# Switches.net
KiCad netlist of a schematic drawn in Altium Designer
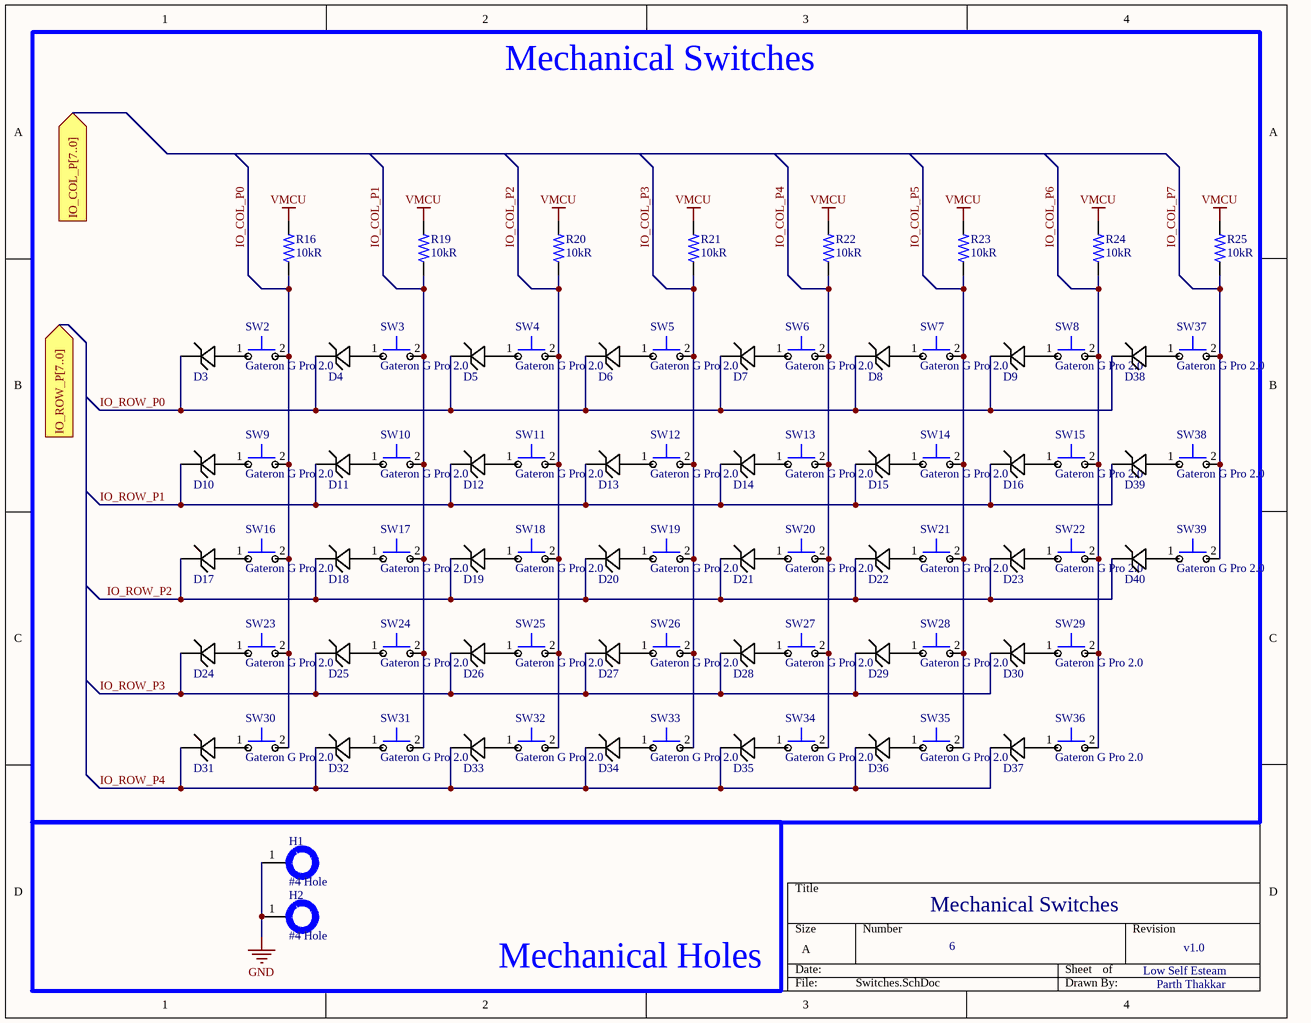
[diagram p0: Switches.SchDoc]

(export (version "E")
  (design (tool "Eeschema 10.0.6"))
  (components
    (comp (ref "D3")
      (value "Diode Schottky")
      (footprint "Diode Schottky")
      (description "Rectifier Diode, Schottky, 1 Phase, 1 Element, 1A, 15V V(RRM), Silicon, DO-214BA")
      (fields
        (field (name "MANUFACTURER") "Microchip")
        (field (name "MANUFACTURER PART NUMBER") "LSM115JE3/TR13")
      )
      (libsource (lib "Keyboard_parts") (part "Diode Schottky"))
    )
    (comp (ref "D4")
      (value "Diode Schottky")
      (footprint "Diode Schottky")
      (description "Rectifier Diode, Schottky, 1 Phase, 1 Element, 1A, 15V V(RRM), Silicon, DO-214BA")
      (fields
        (field (name "MANUFACTURER") "Microchip")
        (field (name "MANUFACTURER PART NUMBER") "LSM115JE3/TR13")
      )
      (libsource (lib "Keyboard_parts") (part "Diode Schottky"))
    )
    (comp (ref "D5")
      (value "Diode Schottky")
      (footprint "Diode Schottky")
      (description "Rectifier Diode, Schottky, 1 Phase, 1 Element, 1A, 15V V(RRM), Silicon, DO-214BA")
      (fields
        (field (name "MANUFACTURER") "Microchip")
        (field (name "MANUFACTURER PART NUMBER") "LSM115JE3/TR13")
      )
      (libsource (lib "Keyboard_parts") (part "Diode Schottky"))
    )
    (comp (ref "D6")
      (value "Diode Schottky")
      (footprint "Diode Schottky")
      (description "Rectifier Diode, Schottky, 1 Phase, 1 Element, 1A, 15V V(RRM), Silicon, DO-214BA")
      (fields
        (field (name "MANUFACTURER") "Microchip")
        (field (name "MANUFACTURER PART NUMBER") "LSM115JE3/TR13")
      )
      (libsource (lib "Keyboard_parts") (part "Diode Schottky"))
    )
    (comp (ref "D7")
      (value "Diode Schottky")
      (footprint "Diode Schottky")
      (description "Rectifier Diode, Schottky, 1 Phase, 1 Element, 1A, 15V V(RRM), Silicon, DO-214BA")
      (fields
        (field (name "MANUFACTURER") "Microchip")
        (field (name "MANUFACTURER PART NUMBER") "LSM115JE3/TR13")
      )
      (libsource (lib "Keyboard_parts") (part "Diode Schottky"))
    )
    (comp (ref "D8")
      (value "Diode Schottky")
      (footprint "Diode Schottky")
      (description "Rectifier Diode, Schottky, 1 Phase, 1 Element, 1A, 15V V(RRM), Silicon, DO-214BA")
      (fields
        (field (name "MANUFACTURER") "Microchip")
        (field (name "MANUFACTURER PART NUMBER") "LSM115JE3/TR13")
      )
      (libsource (lib "Keyboard_parts") (part "Diode Schottky"))
    )
    (comp (ref "D9")
      (value "Diode Schottky")
      (footprint "Diode Schottky")
      (description "Rectifier Diode, Schottky, 1 Phase, 1 Element, 1A, 15V V(RRM), Silicon, DO-214BA")
      (fields
        (field (name "MANUFACTURER") "Microchip")
        (field (name "MANUFACTURER PART NUMBER") "LSM115JE3/TR13")
      )
      (libsource (lib "Keyboard_parts") (part "Diode Schottky"))
    )
    (comp (ref "D10")
      (value "Diode Schottky")
      (footprint "Diode Schottky")
      (description "Rectifier Diode, Schottky, 1 Phase, 1 Element, 1A, 15V V(RRM), Silicon, DO-214BA")
      (fields
        (field (name "MANUFACTURER") "Microchip")
        (field (name "MANUFACTURER PART NUMBER") "LSM115JE3/TR13")
      )
      (libsource (lib "Keyboard_parts") (part "Diode Schottky"))
    )
    (comp (ref "D11")
      (value "Diode Schottky")
      (footprint "Diode Schottky")
      (description "Rectifier Diode, Schottky, 1 Phase, 1 Element, 1A, 15V V(RRM), Silicon, DO-214BA")
      (fields
        (field (name "MANUFACTURER") "Microchip")
        (field (name "MANUFACTURER PART NUMBER") "LSM115JE3/TR13")
      )
      (libsource (lib "Keyboard_parts") (part "Diode Schottky"))
    )
    (comp (ref "D12")
      (value "Diode Schottky")
      (footprint "Diode Schottky")
      (description "Rectifier Diode, Schottky, 1 Phase, 1 Element, 1A, 15V V(RRM), Silicon, DO-214BA")
      (fields
        (field (name "MANUFACTURER") "Microchip")
        (field (name "MANUFACTURER PART NUMBER") "LSM115JE3/TR13")
      )
      (libsource (lib "Keyboard_parts") (part "Diode Schottky"))
    )
    (comp (ref "D13")
      (value "Diode Schottky")
      (footprint "Diode Schottky")
      (description "Rectifier Diode, Schottky, 1 Phase, 1 Element, 1A, 15V V(RRM), Silicon, DO-214BA")
      (fields
        (field (name "MANUFACTURER") "Microchip")
        (field (name "MANUFACTURER PART NUMBER") "LSM115JE3/TR13")
      )
      (libsource (lib "Keyboard_parts") (part "Diode Schottky"))
    )
    (comp (ref "D14")
      (value "Diode Schottky")
      (footprint "Diode Schottky")
      (description "Rectifier Diode, Schottky, 1 Phase, 1 Element, 1A, 15V V(RRM), Silicon, DO-214BA")
      (fields
        (field (name "MANUFACTURER") "Microchip")
        (field (name "MANUFACTURER PART NUMBER") "LSM115JE3/TR13")
      )
      (libsource (lib "Keyboard_parts") (part "Diode Schottky"))
    )
    (comp (ref "D15")
      (value "Diode Schottky")
      (footprint "Diode Schottky")
      (description "Rectifier Diode, Schottky, 1 Phase, 1 Element, 1A, 15V V(RRM), Silicon, DO-214BA")
      (fields
        (field (name "MANUFACTURER") "Microchip")
        (field (name "MANUFACTURER PART NUMBER") "LSM115JE3/TR13")
      )
      (libsource (lib "Keyboard_parts") (part "Diode Schottky"))
    )
    (comp (ref "D16")
      (value "Diode Schottky")
      (footprint "Diode Schottky")
      (description "Rectifier Diode, Schottky, 1 Phase, 1 Element, 1A, 15V V(RRM), Silicon, DO-214BA")
      (fields
        (field (name "MANUFACTURER") "Microchip")
        (field (name "MANUFACTURER PART NUMBER") "LSM115JE3/TR13")
      )
      (libsource (lib "Keyboard_parts") (part "Diode Schottky"))
    )
    (comp (ref "D17")
      (value "Diode Schottky")
      (footprint "Diode Schottky")
      (description "Rectifier Diode, Schottky, 1 Phase, 1 Element, 1A, 15V V(RRM), Silicon, DO-214BA")
      (fields
        (field (name "MANUFACTURER") "Microchip")
        (field (name "MANUFACTURER PART NUMBER") "LSM115JE3/TR13")
      )
      (libsource (lib "Keyboard_parts") (part "Diode Schottky"))
    )
    (comp (ref "D18")
      (value "Diode Schottky")
      (footprint "Diode Schottky")
      (description "Rectifier Diode, Schottky, 1 Phase, 1 Element, 1A, 15V V(RRM), Silicon, DO-214BA")
      (fields
        (field (name "MANUFACTURER") "Microchip")
        (field (name "MANUFACTURER PART NUMBER") "LSM115JE3/TR13")
      )
      (libsource (lib "Keyboard_parts") (part "Diode Schottky"))
    )
    (comp (ref "D19")
      (value "Diode Schottky")
      (footprint "Diode Schottky")
      (description "Rectifier Diode, Schottky, 1 Phase, 1 Element, 1A, 15V V(RRM), Silicon, DO-214BA")
      (fields
        (field (name "MANUFACTURER") "Microchip")
        (field (name "MANUFACTURER PART NUMBER") "LSM115JE3/TR13")
      )
      (libsource (lib "Keyboard_parts") (part "Diode Schottky"))
    )
    (comp (ref "D20")
      (value "Diode Schottky")
      (footprint "Diode Schottky")
      (description "Rectifier Diode, Schottky, 1 Phase, 1 Element, 1A, 15V V(RRM), Silicon, DO-214BA")
      (fields
        (field (name "MANUFACTURER") "Microchip")
        (field (name "MANUFACTURER PART NUMBER") "LSM115JE3/TR13")
      )
      (libsource (lib "Keyboard_parts") (part "Diode Schottky"))
    )
    (comp (ref "D21")
      (value "Diode Schottky")
      (footprint "Diode Schottky")
      (description "Rectifier Diode, Schottky, 1 Phase, 1 Element, 1A, 15V V(RRM), Silicon, DO-214BA")
      (fields
        (field (name "MANUFACTURER") "Microchip")
        (field (name "MANUFACTURER PART NUMBER") "LSM115JE3/TR13")
      )
      (libsource (lib "Keyboard_parts") (part "Diode Schottky"))
    )
    (comp (ref "D22")
      (value "Diode Schottky")
      (footprint "Diode Schottky")
      (description "Rectifier Diode, Schottky, 1 Phase, 1 Element, 1A, 15V V(RRM), Silicon, DO-214BA")
      (fields
        (field (name "MANUFACTURER") "Microchip")
        (field (name "MANUFACTURER PART NUMBER") "LSM115JE3/TR13")
      )
      (libsource (lib "Keyboard_parts") (part "Diode Schottky"))
    )
    (comp (ref "D23")
      (value "Diode Schottky")
      (footprint "Diode Schottky")
      (description "Rectifier Diode, Schottky, 1 Phase, 1 Element, 1A, 15V V(RRM), Silicon, DO-214BA")
      (fields
        (field (name "MANUFACTURER") "Microchip")
        (field (name "MANUFACTURER PART NUMBER") "LSM115JE3/TR13")
      )
      (libsource (lib "Keyboard_parts") (part "Diode Schottky"))
    )
    (comp (ref "D24")
      (value "Diode Schottky")
      (footprint "Diode Schottky")
      (description "Rectifier Diode, Schottky, 1 Phase, 1 Element, 1A, 15V V(RRM), Silicon, DO-214BA")
      (fields
        (field (name "MANUFACTURER") "Microchip")
        (field (name "MANUFACTURER PART NUMBER") "LSM115JE3/TR13")
      )
      (libsource (lib "Keyboard_parts") (part "Diode Schottky"))
    )
    (comp (ref "D25")
      (value "Diode Schottky")
      (footprint "Diode Schottky")
      (description "Rectifier Diode, Schottky, 1 Phase, 1 Element, 1A, 15V V(RRM), Silicon, DO-214BA")
      (fields
        (field (name "MANUFACTURER") "Microchip")
        (field (name "MANUFACTURER PART NUMBER") "LSM115JE3/TR13")
      )
      (libsource (lib "Keyboard_parts") (part "Diode Schottky"))
    )
    (comp (ref "D26")
      (value "Diode Schottky")
      (footprint "Diode Schottky")
      (description "Rectifier Diode, Schottky, 1 Phase, 1 Element, 1A, 15V V(RRM), Silicon, DO-214BA")
      (fields
        (field (name "MANUFACTURER") "Microchip")
        (field (name "MANUFACTURER PART NUMBER") "LSM115JE3/TR13")
      )
      (libsource (lib "Keyboard_parts") (part "Diode Schottky"))
    )
    (comp (ref "D27")
      (value "Diode Schottky")
      (footprint "Diode Schottky")
      (description "Rectifier Diode, Schottky, 1 Phase, 1 Element, 1A, 15V V(RRM), Silicon, DO-214BA")
      (fields
        (field (name "MANUFACTURER") "Microchip")
        (field (name "MANUFACTURER PART NUMBER") "LSM115JE3/TR13")
      )
      (libsource (lib "Keyboard_parts") (part "Diode Schottky"))
    )
    (comp (ref "D28")
      (value "Diode Schottky")
      (footprint "Diode Schottky")
      (description "Rectifier Diode, Schottky, 1 Phase, 1 Element, 1A, 15V V(RRM), Silicon, DO-214BA")
      (fields
        (field (name "MANUFACTURER") "Microchip")
        (field (name "MANUFACTURER PART NUMBER") "LSM115JE3/TR13")
      )
      (libsource (lib "Keyboard_parts") (part "Diode Schottky"))
    )
    (comp (ref "D29")
      (value "Diode Schottky")
      (footprint "Diode Schottky")
      (description "Rectifier Diode, Schottky, 1 Phase, 1 Element, 1A, 15V V(RRM), Silicon, DO-214BA")
      (fields
        (field (name "MANUFACTURER") "Microchip")
        (field (name "MANUFACTURER PART NUMBER") "LSM115JE3/TR13")
      )
      (libsource (lib "Keyboard_parts") (part "Diode Schottky"))
    )
    (comp (ref "D30")
      (value "Diode Schottky")
      (footprint "Diode Schottky")
      (description "Rectifier Diode, Schottky, 1 Phase, 1 Element, 1A, 15V V(RRM), Silicon, DO-214BA")
      (fields
        (field (name "MANUFACTURER") "Microchip")
        (field (name "MANUFACTURER PART NUMBER") "LSM115JE3/TR13")
      )
      (libsource (lib "Keyboard_parts") (part "Diode Schottky"))
    )
    (comp (ref "D31")
      (value "Diode Schottky")
      (footprint "Diode Schottky")
      (description "Rectifier Diode, Schottky, 1 Phase, 1 Element, 1A, 15V V(RRM), Silicon, DO-214BA")
      (fields
        (field (name "MANUFACTURER") "Microchip")
        (field (name "MANUFACTURER PART NUMBER") "LSM115JE3/TR13")
      )
      (libsource (lib "Keyboard_parts") (part "Diode Schottky"))
    )
    (comp (ref "D32")
      (value "Diode Schottky")
      (footprint "Diode Schottky")
      (description "Rectifier Diode, Schottky, 1 Phase, 1 Element, 1A, 15V V(RRM), Silicon, DO-214BA")
      (fields
        (field (name "MANUFACTURER") "Microchip")
        (field (name "MANUFACTURER PART NUMBER") "LSM115JE3/TR13")
      )
      (libsource (lib "Keyboard_parts") (part "Diode Schottky"))
    )
    (comp (ref "D33")
      (value "Diode Schottky")
      (footprint "Diode Schottky")
      (description "Rectifier Diode, Schottky, 1 Phase, 1 Element, 1A, 15V V(RRM), Silicon, DO-214BA")
      (fields
        (field (name "MANUFACTURER") "Microchip")
        (field (name "MANUFACTURER PART NUMBER") "LSM115JE3/TR13")
      )
      (libsource (lib "Keyboard_parts") (part "Diode Schottky"))
    )
    (comp (ref "D34")
      (value "Diode Schottky")
      (footprint "Diode Schottky")
      (description "Rectifier Diode, Schottky, 1 Phase, 1 Element, 1A, 15V V(RRM), Silicon, DO-214BA")
      (fields
        (field (name "MANUFACTURER") "Microchip")
        (field (name "MANUFACTURER PART NUMBER") "LSM115JE3/TR13")
      )
      (libsource (lib "Keyboard_parts") (part "Diode Schottky"))
    )
    (comp (ref "D35")
      (value "Diode Schottky")
      (footprint "Diode Schottky")
      (description "Rectifier Diode, Schottky, 1 Phase, 1 Element, 1A, 15V V(RRM), Silicon, DO-214BA")
      (fields
        (field (name "MANUFACTURER") "Microchip")
        (field (name "MANUFACTURER PART NUMBER") "LSM115JE3/TR13")
      )
      (libsource (lib "Keyboard_parts") (part "Diode Schottky"))
    )
    (comp (ref "D36")
      (value "Diode Schottky")
      (footprint "Diode Schottky")
      (description "Rectifier Diode, Schottky, 1 Phase, 1 Element, 1A, 15V V(RRM), Silicon, DO-214BA")
      (fields
        (field (name "MANUFACTURER") "Microchip")
        (field (name "MANUFACTURER PART NUMBER") "LSM115JE3/TR13")
      )
      (libsource (lib "Keyboard_parts") (part "Diode Schottky"))
    )
    (comp (ref "D37")
      (value "Diode Schottky")
      (footprint "Diode Schottky")
      (description "Rectifier Diode, Schottky, 1 Phase, 1 Element, 1A, 15V V(RRM), Silicon, DO-214BA")
      (fields
        (field (name "MANUFACTURER") "Microchip")
        (field (name "MANUFACTURER PART NUMBER") "LSM115JE3/TR13")
      )
      (libsource (lib "Keyboard_parts") (part "Diode Schottky"))
    )
    (comp (ref "D38")
      (value "Diode Schottky")
      (footprint "Diode Schottky")
      (description "Rectifier Diode, Schottky, 1 Phase, 1 Element, 1A, 15V V(RRM), Silicon, DO-214BA")
      (fields
        (field (name "MANUFACTURER") "Microchip")
        (field (name "MANUFACTURER PART NUMBER") "LSM115JE3/TR13")
      )
      (libsource (lib "Keyboard_parts") (part "Diode Schottky"))
    )
    (comp (ref "D39")
      (value "Diode Schottky")
      (footprint "Diode Schottky")
      (description "Rectifier Diode, Schottky, 1 Phase, 1 Element, 1A, 15V V(RRM), Silicon, DO-214BA")
      (fields
        (field (name "MANUFACTURER") "Microchip")
        (field (name "MANUFACTURER PART NUMBER") "LSM115JE3/TR13")
      )
      (libsource (lib "Keyboard_parts") (part "Diode Schottky"))
    )
    (comp (ref "D40")
      (value "Diode Schottky")
      (footprint "Diode Schottky")
      (description "Rectifier Diode, Schottky, 1 Phase, 1 Element, 1A, 15V V(RRM), Silicon, DO-214BA")
      (fields
        (field (name "MANUFACTURER") "Microchip")
        (field (name "MANUFACTURER PART NUMBER") "LSM115JE3/TR13")
      )
      (libsource (lib "Keyboard_parts") (part "Diode Schottky"))
    )
    (comp (ref "H1") (value "#4 Hole") (footprint "Hole") (libsource (lib "Keyboard_parts") (part "HOLE_#4")))
    (comp (ref "H2") (value "#4 Hole") (footprint "Hole") (libsource (lib "Keyboard_parts") (part "HOLE_#4")))
    (comp (ref "R16")
      (value "10kR")
      (footprint "Resistor 0603")
      (fields
        (field (name "MANUFACTURER") "Yageo")
        (field (name "MANUFACTURER PART NUMBER") "RC0603FR-0710KL")
        (field (name "TOLERANCE") "1%")
      )
      (libsource (lib "Keyboard_parts") (part "RES 10K 0603"))
    )
    (comp (ref "R19")
      (value "10kR")
      (footprint "Resistor 0603")
      (fields
        (field (name "MANUFACTURER") "Yageo")
        (field (name "MANUFACTURER PART NUMBER") "RC0603FR-0710KL")
        (field (name "TOLERANCE") "1%")
      )
      (libsource (lib "Keyboard_parts") (part "RES 10K 0603"))
    )
    (comp (ref "R20")
      (value "10kR")
      (footprint "Resistor 0603")
      (fields
        (field (name "MANUFACTURER") "Yageo")
        (field (name "MANUFACTURER PART NUMBER") "RC0603FR-0710KL")
        (field (name "TOLERANCE") "1%")
      )
      (libsource (lib "Keyboard_parts") (part "RES 10K 0603"))
    )
    (comp (ref "R21")
      (value "10kR")
      (footprint "Resistor 0603")
      (fields
        (field (name "MANUFACTURER") "Yageo")
        (field (name "MANUFACTURER PART NUMBER") "RC0603FR-0710KL")
        (field (name "TOLERANCE") "1%")
      )
      (libsource (lib "Keyboard_parts") (part "RES 10K 0603"))
    )
    (comp (ref "R22")
      (value "10kR")
      (footprint "Resistor 0603")
      (fields
        (field (name "MANUFACTURER") "Yageo")
        (field (name "MANUFACTURER PART NUMBER") "RC0603FR-0710KL")
        (field (name "TOLERANCE") "1%")
      )
      (libsource (lib "Keyboard_parts") (part "RES 10K 0603"))
    )
    (comp (ref "R23")
      (value "10kR")
      (footprint "Resistor 0603")
      (fields
        (field (name "MANUFACTURER") "Yageo")
        (field (name "MANUFACTURER PART NUMBER") "RC0603FR-0710KL")
        (field (name "TOLERANCE") "1%")
      )
      (libsource (lib "Keyboard_parts") (part "RES 10K 0603"))
    )
    (comp (ref "R24")
      (value "10kR")
      (footprint "Resistor 0603")
      (fields
        (field (name "MANUFACTURER") "Yageo")
        (field (name "MANUFACTURER PART NUMBER") "RC0603FR-0710KL")
        (field (name "TOLERANCE") "1%")
      )
      (libsource (lib "Keyboard_parts") (part "RES 10K 0603"))
    )
    (comp (ref "R25")
      (value "10kR")
      (footprint "Resistor 0603")
      (fields
        (field (name "MANUFACTURER") "Yageo")
        (field (name "MANUFACTURER PART NUMBER") "RC0603FR-0710KL")
        (field (name "TOLERANCE") "1%")
      )
      (libsource (lib "Keyboard_parts") (part "RES 10K 0603"))
    )
    (comp (ref "SW2")
      (value "Gateron G Pro 2.0")
      (footprint "Mechanical Switch")
      (description "Gateron G Pro 2.0, The 3-Pin switches are compatible with any 3-Pin/5-Pin MX mechanical keyboard")
      (libsource (lib "Keyboard_parts") (part "Gateron G Pro 2.0"))
    )
    (comp (ref "SW3")
      (value "Gateron G Pro 2.0")
      (footprint "Mechanical Switch")
      (description "Gateron G Pro 2.0, The 3-Pin switches are compatible with any 3-Pin/5-Pin MX mechanical keyboard")
      (libsource (lib "Keyboard_parts") (part "Gateron G Pro 2.0"))
    )
    (comp (ref "SW4")
      (value "Gateron G Pro 2.0")
      (footprint "Mechanical Switch")
      (description "Gateron G Pro 2.0, The 3-Pin switches are compatible with any 3-Pin/5-Pin MX mechanical keyboard")
      (libsource (lib "Keyboard_parts") (part "Gateron G Pro 2.0"))
    )
    (comp (ref "SW5")
      (value "Gateron G Pro 2.0")
      (footprint "Mechanical Switch")
      (description "Gateron G Pro 2.0, The 3-Pin switches are compatible with any 3-Pin/5-Pin MX mechanical keyboard")
      (libsource (lib "Keyboard_parts") (part "Gateron G Pro 2.0"))
    )
    (comp (ref "SW6")
      (value "Gateron G Pro 2.0")
      (footprint "Mechanical Switch")
      (description "Gateron G Pro 2.0, The 3-Pin switches are compatible with any 3-Pin/5-Pin MX mechanical keyboard")
      (libsource (lib "Keyboard_parts") (part "Gateron G Pro 2.0"))
    )
    (comp (ref "SW7")
      (value "Gateron G Pro 2.0")
      (footprint "Mechanical Switch")
      (description "Gateron G Pro 2.0, The 3-Pin switches are compatible with any 3-Pin/5-Pin MX mechanical keyboard")
      (libsource (lib "Keyboard_parts") (part "Gateron G Pro 2.0"))
    )
    (comp (ref "SW8")
      (value "Gateron G Pro 2.0")
      (footprint "Mechanical Switch")
      (description "Gateron G Pro 2.0, The 3-Pin switches are compatible with any 3-Pin/5-Pin MX mechanical keyboard")
      (libsource (lib "Keyboard_parts") (part "Gateron G Pro 2.0"))
    )
    (comp (ref "SW9")
      (value "Gateron G Pro 2.0")
      (footprint "Mechanical Switch")
      (description "Gateron G Pro 2.0, The 3-Pin switches are compatible with any 3-Pin/5-Pin MX mechanical keyboard")
      (libsource (lib "Keyboard_parts") (part "Gateron G Pro 2.0"))
    )
    (comp (ref "SW10")
      (value "Gateron G Pro 2.0")
      (footprint "Mechanical Switch")
      (description "Gateron G Pro 2.0, The 3-Pin switches are compatible with any 3-Pin/5-Pin MX mechanical keyboard")
      (libsource (lib "Keyboard_parts") (part "Gateron G Pro 2.0"))
    )
    (comp (ref "SW11")
      (value "Gateron G Pro 2.0")
      (footprint "Mechanical Switch")
      (description "Gateron G Pro 2.0, The 3-Pin switches are compatible with any 3-Pin/5-Pin MX mechanical keyboard")
      (libsource (lib "Keyboard_parts") (part "Gateron G Pro 2.0"))
    )
    (comp (ref "SW12")
      (value "Gateron G Pro 2.0")
      (footprint "Mechanical Switch")
      (description "Gateron G Pro 2.0, The 3-Pin switches are compatible with any 3-Pin/5-Pin MX mechanical keyboard")
      (libsource (lib "Keyboard_parts") (part "Gateron G Pro 2.0"))
    )
    (comp (ref "SW13")
      (value "Gateron G Pro 2.0")
      (footprint "Mechanical Switch")
      (description "Gateron G Pro 2.0, The 3-Pin switches are compatible with any 3-Pin/5-Pin MX mechanical keyboard")
      (libsource (lib "Keyboard_parts") (part "Gateron G Pro 2.0"))
    )
    (comp (ref "SW14")
      (value "Gateron G Pro 2.0")
      (footprint "Mechanical Switch")
      (description "Gateron G Pro 2.0, The 3-Pin switches are compatible with any 3-Pin/5-Pin MX mechanical keyboard")
      (libsource (lib "Keyboard_parts") (part "Gateron G Pro 2.0"))
    )
    (comp (ref "SW15")
      (value "Gateron G Pro 2.0")
      (footprint "Mechanical Switch")
      (description "Gateron G Pro 2.0, The 3-Pin switches are compatible with any 3-Pin/5-Pin MX mechanical keyboard")
      (libsource (lib "Keyboard_parts") (part "Gateron G Pro 2.0"))
    )
    (comp (ref "SW16")
      (value "Gateron G Pro 2.0")
      (footprint "Mechanical Switch")
      (description "Gateron G Pro 2.0, The 3-Pin switches are compatible with any 3-Pin/5-Pin MX mechanical keyboard")
      (libsource (lib "Keyboard_parts") (part "Gateron G Pro 2.0"))
    )
    (comp (ref "SW17")
      (value "Gateron G Pro 2.0")
      (footprint "Mechanical Switch")
      (description "Gateron G Pro 2.0, The 3-Pin switches are compatible with any 3-Pin/5-Pin MX mechanical keyboard")
      (libsource (lib "Keyboard_parts") (part "Gateron G Pro 2.0"))
    )
    (comp (ref "SW18")
      (value "Gateron G Pro 2.0")
      (footprint "Mechanical Switch")
      (description "Gateron G Pro 2.0, The 3-Pin switches are compatible with any 3-Pin/5-Pin MX mechanical keyboard")
      (libsource (lib "Keyboard_parts") (part "Gateron G Pro 2.0"))
    )
    (comp (ref "SW19")
      (value "Gateron G Pro 2.0")
      (footprint "Mechanical Switch")
      (description "Gateron G Pro 2.0, The 3-Pin switches are compatible with any 3-Pin/5-Pin MX mechanical keyboard")
      (libsource (lib "Keyboard_parts") (part "Gateron G Pro 2.0"))
    )
    (comp (ref "SW20")
      (value "Gateron G Pro 2.0")
      (footprint "Mechanical Switch")
      (description "Gateron G Pro 2.0, The 3-Pin switches are compatible with any 3-Pin/5-Pin MX mechanical keyboard")
      (libsource (lib "Keyboard_parts") (part "Gateron G Pro 2.0"))
    )
    (comp (ref "SW21")
      (value "Gateron G Pro 2.0")
      (footprint "Mechanical Switch")
      (description "Gateron G Pro 2.0, The 3-Pin switches are compatible with any 3-Pin/5-Pin MX mechanical keyboard")
      (libsource (lib "Keyboard_parts") (part "Gateron G Pro 2.0"))
    )
    (comp (ref "SW22")
      (value "Gateron G Pro 2.0")
      (footprint "Mechanical Switch")
      (description "Gateron G Pro 2.0, The 3-Pin switches are compatible with any 3-Pin/5-Pin MX mechanical keyboard")
      (libsource (lib "Keyboard_parts") (part "Gateron G Pro 2.0"))
    )
    (comp (ref "SW23")
      (value "Gateron G Pro 2.0")
      (footprint "Mechanical Switch")
      (description "Gateron G Pro 2.0, The 3-Pin switches are compatible with any 3-Pin/5-Pin MX mechanical keyboard")
      (libsource (lib "Keyboard_parts") (part "Gateron G Pro 2.0"))
    )
    (comp (ref "SW24")
      (value "Gateron G Pro 2.0")
      (footprint "Mechanical Switch")
      (description "Gateron G Pro 2.0, The 3-Pin switches are compatible with any 3-Pin/5-Pin MX mechanical keyboard")
      (libsource (lib "Keyboard_parts") (part "Gateron G Pro 2.0"))
    )
    (comp (ref "SW25")
      (value "Gateron G Pro 2.0")
      (footprint "Mechanical Switch")
      (description "Gateron G Pro 2.0, The 3-Pin switches are compatible with any 3-Pin/5-Pin MX mechanical keyboard")
      (libsource (lib "Keyboard_parts") (part "Gateron G Pro 2.0"))
    )
    (comp (ref "SW26")
      (value "Gateron G Pro 2.0")
      (footprint "Mechanical Switch")
      (description "Gateron G Pro 2.0, The 3-Pin switches are compatible with any 3-Pin/5-Pin MX mechanical keyboard")
      (libsource (lib "Keyboard_parts") (part "Gateron G Pro 2.0"))
    )
    (comp (ref "SW27")
      (value "Gateron G Pro 2.0")
      (footprint "Mechanical Switch")
      (description "Gateron G Pro 2.0, The 3-Pin switches are compatible with any 3-Pin/5-Pin MX mechanical keyboard")
      (libsource (lib "Keyboard_parts") (part "Gateron G Pro 2.0"))
    )
    (comp (ref "SW28")
      (value "Gateron G Pro 2.0")
      (footprint "Mechanical Switch")
      (description "Gateron G Pro 2.0, The 3-Pin switches are compatible with any 3-Pin/5-Pin MX mechanical keyboard")
      (libsource (lib "Keyboard_parts") (part "Gateron G Pro 2.0"))
    )
    (comp (ref "SW29")
      (value "Gateron G Pro 2.0")
      (footprint "Mechanical Switch")
      (description "Gateron G Pro 2.0, The 3-Pin switches are compatible with any 3-Pin/5-Pin MX mechanical keyboard")
      (libsource (lib "Keyboard_parts") (part "Gateron G Pro 2.0"))
    )
    (comp (ref "SW30")
      (value "Gateron G Pro 2.0")
      (footprint "Mechanical Switch")
      (description "Gateron G Pro 2.0, The 3-Pin switches are compatible with any 3-Pin/5-Pin MX mechanical keyboard")
      (libsource (lib "Keyboard_parts") (part "Gateron G Pro 2.0"))
    )
    (comp (ref "SW31")
      (value "Gateron G Pro 2.0")
      (footprint "Mechanical Switch")
      (description "Gateron G Pro 2.0, The 3-Pin switches are compatible with any 3-Pin/5-Pin MX mechanical keyboard")
      (libsource (lib "Keyboard_parts") (part "Gateron G Pro 2.0"))
    )
    (comp (ref "SW32")
      (value "Gateron G Pro 2.0")
      (footprint "Mechanical Switch")
      (description "Gateron G Pro 2.0, The 3-Pin switches are compatible with any 3-Pin/5-Pin MX mechanical keyboard")
      (libsource (lib "Keyboard_parts") (part "Gateron G Pro 2.0"))
    )
    (comp (ref "SW33")
      (value "Gateron G Pro 2.0")
      (footprint "Mechanical Switch")
      (description "Gateron G Pro 2.0, The 3-Pin switches are compatible with any 3-Pin/5-Pin MX mechanical keyboard")
      (libsource (lib "Keyboard_parts") (part "Gateron G Pro 2.0"))
    )
    (comp (ref "SW34")
      (value "Gateron G Pro 2.0")
      (footprint "Mechanical Switch")
      (description "Gateron G Pro 2.0, The 3-Pin switches are compatible with any 3-Pin/5-Pin MX mechanical keyboard")
      (libsource (lib "Keyboard_parts") (part "Gateron G Pro 2.0"))
    )
    (comp (ref "SW35")
      (value "Gateron G Pro 2.0")
      (footprint "Mechanical Switch")
      (description "Gateron G Pro 2.0, The 3-Pin switches are compatible with any 3-Pin/5-Pin MX mechanical keyboard")
      (libsource (lib "Keyboard_parts") (part "Gateron G Pro 2.0"))
    )
    (comp (ref "SW36")
      (value "Gateron G Pro 2.0")
      (footprint "Mechanical Switch")
      (description "Gateron G Pro 2.0, The 3-Pin switches are compatible with any 3-Pin/5-Pin MX mechanical keyboard")
      (libsource (lib "Keyboard_parts") (part "Gateron G Pro 2.0"))
    )
    (comp (ref "SW37")
      (value "Gateron G Pro 2.0")
      (footprint "Mechanical Switch")
      (description "Gateron G Pro 2.0, The 3-Pin switches are compatible with any 3-Pin/5-Pin MX mechanical keyboard")
      (libsource (lib "Keyboard_parts") (part "Gateron G Pro 2.0"))
    )
    (comp (ref "SW38")
      (value "Gateron G Pro 2.0")
      (footprint "Mechanical Switch")
      (description "Gateron G Pro 2.0, The 3-Pin switches are compatible with any 3-Pin/5-Pin MX mechanical keyboard")
      (libsource (lib "Keyboard_parts") (part "Gateron G Pro 2.0"))
    )
    (comp (ref "SW39")
      (value "Gateron G Pro 2.0")
      (footprint "Mechanical Switch")
      (description "Gateron G Pro 2.0, The 3-Pin switches are compatible with any 3-Pin/5-Pin MX mechanical keyboard")
      (libsource (lib "Keyboard_parts") (part "Gateron G Pro 2.0"))
    )
  )
  (nets
    (net (code "4") (name "/IO_COL_P0") (class "Default")
      (node (ref "R16") (pin "1") (pinfunction "1_1") (pintype "passive"))
      (node (ref "SW16") (pin "2") (pinfunction "2_2") (pintype "passive"))
      (node (ref "SW2") (pin "2") (pinfunction "2_2") (pintype "passive"))
      (node (ref "SW23") (pin "2") (pinfunction "2_2") (pintype "passive"))
      (node (ref "SW30") (pin "2") (pinfunction "2_2") (pintype "passive"))
      (node (ref "SW9") (pin "2") (pinfunction "2_2") (pintype "passive"))
    )
    (net (code "5") (name "/IO_COL_P1") (class "Default")
      (node (ref "R19") (pin "1") (pinfunction "1_1") (pintype "passive"))
      (node (ref "SW10") (pin "2") (pinfunction "2_2") (pintype "passive"))
      (node (ref "SW17") (pin "2") (pinfunction "2_2") (pintype "passive"))
      (node (ref "SW24") (pin "2") (pinfunction "2_2") (pintype "passive"))
      (node (ref "SW3") (pin "2") (pinfunction "2_2") (pintype "passive"))
      (node (ref "SW31") (pin "2") (pinfunction "2_2") (pintype "passive"))
    )
    (net (code "6") (name "/IO_COL_P2") (class "Default")
      (node (ref "R20") (pin "1") (pinfunction "1_1") (pintype "passive"))
      (node (ref "SW11") (pin "2") (pinfunction "2_2") (pintype "passive"))
      (node (ref "SW18") (pin "2") (pinfunction "2_2") (pintype "passive"))
      (node (ref "SW25") (pin "2") (pinfunction "2_2") (pintype "passive"))
      (node (ref "SW32") (pin "2") (pinfunction "2_2") (pintype "passive"))
      (node (ref "SW4") (pin "2") (pinfunction "2_2") (pintype "passive"))
    )
    (net (code "7") (name "/IO_COL_P3") (class "Default")
      (node (ref "R21") (pin "1") (pinfunction "1_1") (pintype "passive"))
      (node (ref "SW12") (pin "2") (pinfunction "2_2") (pintype "passive"))
      (node (ref "SW19") (pin "2") (pinfunction "2_2") (pintype "passive"))
      (node (ref "SW26") (pin "2") (pinfunction "2_2") (pintype "passive"))
      (node (ref "SW33") (pin "2") (pinfunction "2_2") (pintype "passive"))
      (node (ref "SW5") (pin "2") (pinfunction "2_2") (pintype "passive"))
    )
    (net (code "8") (name "/IO_COL_P4") (class "Default")
      (node (ref "R22") (pin "1") (pinfunction "1_1") (pintype "passive"))
      (node (ref "SW13") (pin "2") (pinfunction "2_2") (pintype "passive"))
      (node (ref "SW20") (pin "2") (pinfunction "2_2") (pintype "passive"))
      (node (ref "SW27") (pin "2") (pinfunction "2_2") (pintype "passive"))
      (node (ref "SW34") (pin "2") (pinfunction "2_2") (pintype "passive"))
      (node (ref "SW6") (pin "2") (pinfunction "2_2") (pintype "passive"))
    )
    (net (code "9") (name "/IO_COL_P5") (class "Default")
      (node (ref "R23") (pin "1") (pinfunction "1_1") (pintype "passive"))
      (node (ref "SW14") (pin "2") (pinfunction "2_2") (pintype "passive"))
      (node (ref "SW21") (pin "2") (pinfunction "2_2") (pintype "passive"))
      (node (ref "SW28") (pin "2") (pinfunction "2_2") (pintype "passive"))
      (node (ref "SW35") (pin "2") (pinfunction "2_2") (pintype "passive"))
      (node (ref "SW7") (pin "2") (pinfunction "2_2") (pintype "passive"))
    )
    (net (code "10") (name "/IO_COL_P6") (class "Default")
      (node (ref "R24") (pin "1") (pinfunction "1_1") (pintype "passive"))
      (node (ref "SW15") (pin "2") (pinfunction "2_2") (pintype "passive"))
      (node (ref "SW22") (pin "2") (pinfunction "2_2") (pintype "passive"))
      (node (ref "SW29") (pin "2") (pinfunction "2_2") (pintype "passive"))
      (node (ref "SW36") (pin "2") (pinfunction "2_2") (pintype "passive"))
      (node (ref "SW8") (pin "2") (pinfunction "2_2") (pintype "passive"))
    )
    (net (code "11") (name "/IO_COL_P7") (class "Default")
      (node (ref "R25") (pin "1") (pinfunction "1_1") (pintype "passive"))
      (node (ref "SW37") (pin "2") (pinfunction "2_2") (pintype "passive"))
      (node (ref "SW38") (pin "2") (pinfunction "2_2") (pintype "passive"))
      (node (ref "SW39") (pin "2") (pinfunction "2_2") (pintype "passive"))
    )
    (net (code "13") (name "/IO_ROW_P0") (class "Default")
      (node (ref "D3") (pin "1") (pinfunction "1_1") (pintype "passive"))
      (node (ref "D38") (pin "1") (pinfunction "1_1") (pintype "passive"))
      (node (ref "D4") (pin "1") (pinfunction "1_1") (pintype "passive"))
      (node (ref "D5") (pin "1") (pinfunction "1_1") (pintype "passive"))
      (node (ref "D6") (pin "1") (pinfunction "1_1") (pintype "passive"))
      (node (ref "D7") (pin "1") (pinfunction "1_1") (pintype "passive"))
      (node (ref "D8") (pin "1") (pinfunction "1_1") (pintype "passive"))
      (node (ref "D9") (pin "1") (pinfunction "1_1") (pintype "passive"))
    )
    (net (code "14") (name "/IO_ROW_P1") (class "Default")
      (node (ref "D10") (pin "1") (pinfunction "1_1") (pintype "passive"))
      (node (ref "D11") (pin "1") (pinfunction "1_1") (pintype "passive"))
      (node (ref "D12") (pin "1") (pinfunction "1_1") (pintype "passive"))
      (node (ref "D13") (pin "1") (pinfunction "1_1") (pintype "passive"))
      (node (ref "D14") (pin "1") (pinfunction "1_1") (pintype "passive"))
      (node (ref "D15") (pin "1") (pinfunction "1_1") (pintype "passive"))
      (node (ref "D16") (pin "1") (pinfunction "1_1") (pintype "passive"))
      (node (ref "D39") (pin "1") (pinfunction "1_1") (pintype "passive"))
    )
    (net (code "15") (name "/IO_ROW_P2") (class "Default")
      (node (ref "D17") (pin "1") (pinfunction "1_1") (pintype "passive"))
      (node (ref "D18") (pin "1") (pinfunction "1_1") (pintype "passive"))
      (node (ref "D19") (pin "1") (pinfunction "1_1") (pintype "passive"))
      (node (ref "D20") (pin "1") (pinfunction "1_1") (pintype "passive"))
      (node (ref "D21") (pin "1") (pinfunction "1_1") (pintype "passive"))
      (node (ref "D22") (pin "1") (pinfunction "1_1") (pintype "passive"))
      (node (ref "D23") (pin "1") (pinfunction "1_1") (pintype "passive"))
      (node (ref "D40") (pin "1") (pinfunction "1_1") (pintype "passive"))
    )
    (net (code "16") (name "/IO_ROW_P3") (class "Default")
      (node (ref "D24") (pin "1") (pinfunction "1_1") (pintype "passive"))
      (node (ref "D25") (pin "1") (pinfunction "1_1") (pintype "passive"))
      (node (ref "D26") (pin "1") (pinfunction "1_1") (pintype "passive"))
      (node (ref "D27") (pin "1") (pinfunction "1_1") (pintype "passive"))
      (node (ref "D28") (pin "1") (pinfunction "1_1") (pintype "passive"))
      (node (ref "D29") (pin "1") (pinfunction "1_1") (pintype "passive"))
      (node (ref "D30") (pin "1") (pinfunction "1_1") (pintype "passive"))
    )
    (net (code "17") (name "/IO_ROW_P4") (class "Default")
      (node (ref "D31") (pin "1") (pinfunction "1_1") (pintype "passive"))
      (node (ref "D32") (pin "1") (pinfunction "1_1") (pintype "passive"))
      (node (ref "D33") (pin "1") (pinfunction "1_1") (pintype "passive"))
      (node (ref "D34") (pin "1") (pinfunction "1_1") (pintype "passive"))
      (node (ref "D35") (pin "1") (pinfunction "1_1") (pintype "passive"))
      (node (ref "D36") (pin "1") (pinfunction "1_1") (pintype "passive"))
      (node (ref "D37") (pin "1") (pinfunction "1_1") (pintype "passive"))
    )
    (net (code "19") (name "GND") (class "Default")
      (node (ref "H1") (pin "1") (pinfunction "1_1") (pintype "passive"))
      (node (ref "H2") (pin "1") (pinfunction "1_1") (pintype "passive"))
    )
    (net (code "20") (name "Net-(D3-Pad2)") (class "Default")
      (node (ref "D3") (pin "2") (pinfunction "2_2") (pintype "passive"))
      (node (ref "SW2") (pin "1") (pinfunction "1_1") (pintype "passive"))
    )
    (net (code "21") (name "Net-(D4-Pad2)") (class "Default")
      (node (ref "D4") (pin "2") (pinfunction "2_2") (pintype "passive"))
      (node (ref "SW3") (pin "1") (pinfunction "1_1") (pintype "passive"))
    )
    (net (code "22") (name "Net-(D5-Pad2)") (class "Default")
      (node (ref "D5") (pin "2") (pinfunction "2_2") (pintype "passive"))
      (node (ref "SW4") (pin "1") (pinfunction "1_1") (pintype "passive"))
    )
    (net (code "23") (name "Net-(D6-Pad2)") (class "Default")
      (node (ref "D6") (pin "2") (pinfunction "2_2") (pintype "passive"))
      (node (ref "SW5") (pin "1") (pinfunction "1_1") (pintype "passive"))
    )
    (net (code "24") (name "Net-(D7-Pad2)") (class "Default")
      (node (ref "D7") (pin "2") (pinfunction "2_2") (pintype "passive"))
      (node (ref "SW6") (pin "1") (pinfunction "1_1") (pintype "passive"))
    )
    (net (code "25") (name "Net-(D8-Pad2)") (class "Default")
      (node (ref "D8") (pin "2") (pinfunction "2_2") (pintype "passive"))
      (node (ref "SW7") (pin "1") (pinfunction "1_1") (pintype "passive"))
    )
    (net (code "26") (name "Net-(D9-Pad2)") (class "Default")
      (node (ref "D9") (pin "2") (pinfunction "2_2") (pintype "passive"))
      (node (ref "SW8") (pin "1") (pinfunction "1_1") (pintype "passive"))
    )
    (net (code "27") (name "Net-(D10-Pad2)") (class "Default")
      (node (ref "D10") (pin "2") (pinfunction "2_2") (pintype "passive"))
      (node (ref "SW9") (pin "1") (pinfunction "1_1") (pintype "passive"))
    )
    (net (code "28") (name "Net-(D11-Pad2)") (class "Default")
      (node (ref "D11") (pin "2") (pinfunction "2_2") (pintype "passive"))
      (node (ref "SW10") (pin "1") (pinfunction "1_1") (pintype "passive"))
    )
    (net (code "29") (name "Net-(D12-Pad2)") (class "Default")
      (node (ref "D12") (pin "2") (pinfunction "2_2") (pintype "passive"))
      (node (ref "SW11") (pin "1") (pinfunction "1_1") (pintype "passive"))
    )
    (net (code "30") (name "Net-(D13-Pad2)") (class "Default")
      (node (ref "D13") (pin "2") (pinfunction "2_2") (pintype "passive"))
      (node (ref "SW12") (pin "1") (pinfunction "1_1") (pintype "passive"))
    )
    (net (code "31") (name "Net-(D14-Pad2)") (class "Default")
      (node (ref "D14") (pin "2") (pinfunction "2_2") (pintype "passive"))
      (node (ref "SW13") (pin "1") (pinfunction "1_1") (pintype "passive"))
    )
    (net (code "32") (name "Net-(D15-Pad2)") (class "Default")
      (node (ref "D15") (pin "2") (pinfunction "2_2") (pintype "passive"))
      (node (ref "SW14") (pin "1") (pinfunction "1_1") (pintype "passive"))
    )
    (net (code "33") (name "Net-(D16-Pad2)") (class "Default")
      (node (ref "D16") (pin "2") (pinfunction "2_2") (pintype "passive"))
      (node (ref "SW15") (pin "1") (pinfunction "1_1") (pintype "passive"))
    )
    (net (code "34") (name "Net-(D17-Pad2)") (class "Default")
      (node (ref "D17") (pin "2") (pinfunction "2_2") (pintype "passive"))
      (node (ref "SW16") (pin "1") (pinfunction "1_1") (pintype "passive"))
    )
    (net (code "35") (name "Net-(D18-Pad2)") (class "Default")
      (node (ref "D18") (pin "2") (pinfunction "2_2") (pintype "passive"))
      (node (ref "SW17") (pin "1") (pinfunction "1_1") (pintype "passive"))
    )
    (net (code "36") (name "Net-(D19-Pad2)") (class "Default")
      (node (ref "D19") (pin "2") (pinfunction "2_2") (pintype "passive"))
      (node (ref "SW18") (pin "1") (pinfunction "1_1") (pintype "passive"))
    )
    (net (code "37") (name "Net-(D20-Pad2)") (class "Default")
      (node (ref "D20") (pin "2") (pinfunction "2_2") (pintype "passive"))
      (node (ref "SW19") (pin "1") (pinfunction "1_1") (pintype "passive"))
    )
    (net (code "38") (name "Net-(D21-Pad2)") (class "Default")
      (node (ref "D21") (pin "2") (pinfunction "2_2") (pintype "passive"))
      (node (ref "SW20") (pin "1") (pinfunction "1_1") (pintype "passive"))
    )
    (net (code "39") (name "Net-(D22-Pad2)") (class "Default")
      (node (ref "D22") (pin "2") (pinfunction "2_2") (pintype "passive"))
      (node (ref "SW21") (pin "1") (pinfunction "1_1") (pintype "passive"))
    )
    (net (code "40") (name "Net-(D23-Pad2)") (class "Default")
      (node (ref "D23") (pin "2") (pinfunction "2_2") (pintype "passive"))
      (node (ref "SW22") (pin "1") (pinfunction "1_1") (pintype "passive"))
    )
    (net (code "41") (name "Net-(D24-Pad2)") (class "Default")
      (node (ref "D24") (pin "2") (pinfunction "2_2") (pintype "passive"))
      (node (ref "SW23") (pin "1") (pinfunction "1_1") (pintype "passive"))
    )
    (net (code "42") (name "Net-(D25-Pad2)") (class "Default")
      (node (ref "D25") (pin "2") (pinfunction "2_2") (pintype "passive"))
      (node (ref "SW24") (pin "1") (pinfunction "1_1") (pintype "passive"))
    )
    (net (code "43") (name "Net-(D26-Pad2)") (class "Default")
      (node (ref "D26") (pin "2") (pinfunction "2_2") (pintype "passive"))
      (node (ref "SW25") (pin "1") (pinfunction "1_1") (pintype "passive"))
    )
    (net (code "44") (name "Net-(D27-Pad2)") (class "Default")
      (node (ref "D27") (pin "2") (pinfunction "2_2") (pintype "passive"))
      (node (ref "SW26") (pin "1") (pinfunction "1_1") (pintype "passive"))
    )
    (net (code "45") (name "Net-(D28-Pad2)") (class "Default")
      (node (ref "D28") (pin "2") (pinfunction "2_2") (pintype "passive"))
      (node (ref "SW27") (pin "1") (pinfunction "1_1") (pintype "passive"))
    )
    (net (code "46") (name "Net-(D29-Pad2)") (class "Default")
      (node (ref "D29") (pin "2") (pinfunction "2_2") (pintype "passive"))
      (node (ref "SW28") (pin "1") (pinfunction "1_1") (pintype "passive"))
    )
    (net (code "47") (name "Net-(D30-Pad2)") (class "Default")
      (node (ref "D30") (pin "2") (pinfunction "2_2") (pintype "passive"))
      (node (ref "SW29") (pin "1") (pinfunction "1_1") (pintype "passive"))
    )
    (net (code "48") (name "Net-(D31-Pad2)") (class "Default")
      (node (ref "D31") (pin "2") (pinfunction "2_2") (pintype "passive"))
      (node (ref "SW30") (pin "1") (pinfunction "1_1") (pintype "passive"))
    )
    (net (code "49") (name "Net-(D32-Pad2)") (class "Default")
      (node (ref "D32") (pin "2") (pinfunction "2_2") (pintype "passive"))
      (node (ref "SW31") (pin "1") (pinfunction "1_1") (pintype "passive"))
    )
    (net (code "50") (name "Net-(D33-Pad2)") (class "Default")
      (node (ref "D33") (pin "2") (pinfunction "2_2") (pintype "passive"))
      (node (ref "SW32") (pin "1") (pinfunction "1_1") (pintype "passive"))
    )
    (net (code "51") (name "Net-(D34-Pad2)") (class "Default")
      (node (ref "D34") (pin "2") (pinfunction "2_2") (pintype "passive"))
      (node (ref "SW33") (pin "1") (pinfunction "1_1") (pintype "passive"))
    )
    (net (code "52") (name "Net-(D35-Pad2)") (class "Default")
      (node (ref "D35") (pin "2") (pinfunction "2_2") (pintype "passive"))
      (node (ref "SW34") (pin "1") (pinfunction "1_1") (pintype "passive"))
    )
    (net (code "53") (name "Net-(D36-Pad2)") (class "Default")
      (node (ref "D36") (pin "2") (pinfunction "2_2") (pintype "passive"))
      (node (ref "SW35") (pin "1") (pinfunction "1_1") (pintype "passive"))
    )
    (net (code "54") (name "Net-(D37-Pad2)") (class "Default")
      (node (ref "D37") (pin "2") (pinfunction "2_2") (pintype "passive"))
      (node (ref "SW36") (pin "1") (pinfunction "1_1") (pintype "passive"))
    )
    (net (code "55") (name "Net-(D38-Pad2)") (class "Default")
      (node (ref "D38") (pin "2") (pinfunction "2_2") (pintype "passive"))
      (node (ref "SW37") (pin "1") (pinfunction "1_1") (pintype "passive"))
    )
    (net (code "56") (name "Net-(D39-Pad2)") (class "Default")
      (node (ref "D39") (pin "2") (pinfunction "2_2") (pintype "passive"))
      (node (ref "SW38") (pin "1") (pinfunction "1_1") (pintype "passive"))
    )
    (net (code "57") (name "Net-(D40-Pad2)") (class "Default")
      (node (ref "D40") (pin "2") (pinfunction "2_2") (pintype "passive"))
      (node (ref "SW39") (pin "1") (pinfunction "1_1") (pintype "passive"))
    )
    (net (code "58") (name "VMCU") (class "Default")
      (node (ref "R16") (pin "2") (pinfunction "2_2") (pintype "passive"))
      (node (ref "R19") (pin "2") (pinfunction "2_2") (pintype "passive"))
      (node (ref "R20") (pin "2") (pinfunction "2_2") (pintype "passive"))
      (node (ref "R21") (pin "2") (pinfunction "2_2") (pintype "passive"))
      (node (ref "R22") (pin "2") (pinfunction "2_2") (pintype "passive"))
      (node (ref "R23") (pin "2") (pinfunction "2_2") (pintype "passive"))
      (node (ref "R24") (pin "2") (pinfunction "2_2") (pintype "passive"))
      (node (ref "R25") (pin "2") (pinfunction "2_2") (pintype "passive"))
    )
  )
)
